# Peripherals.net
KiCad netlist of a schematic drawn in Altium Designer
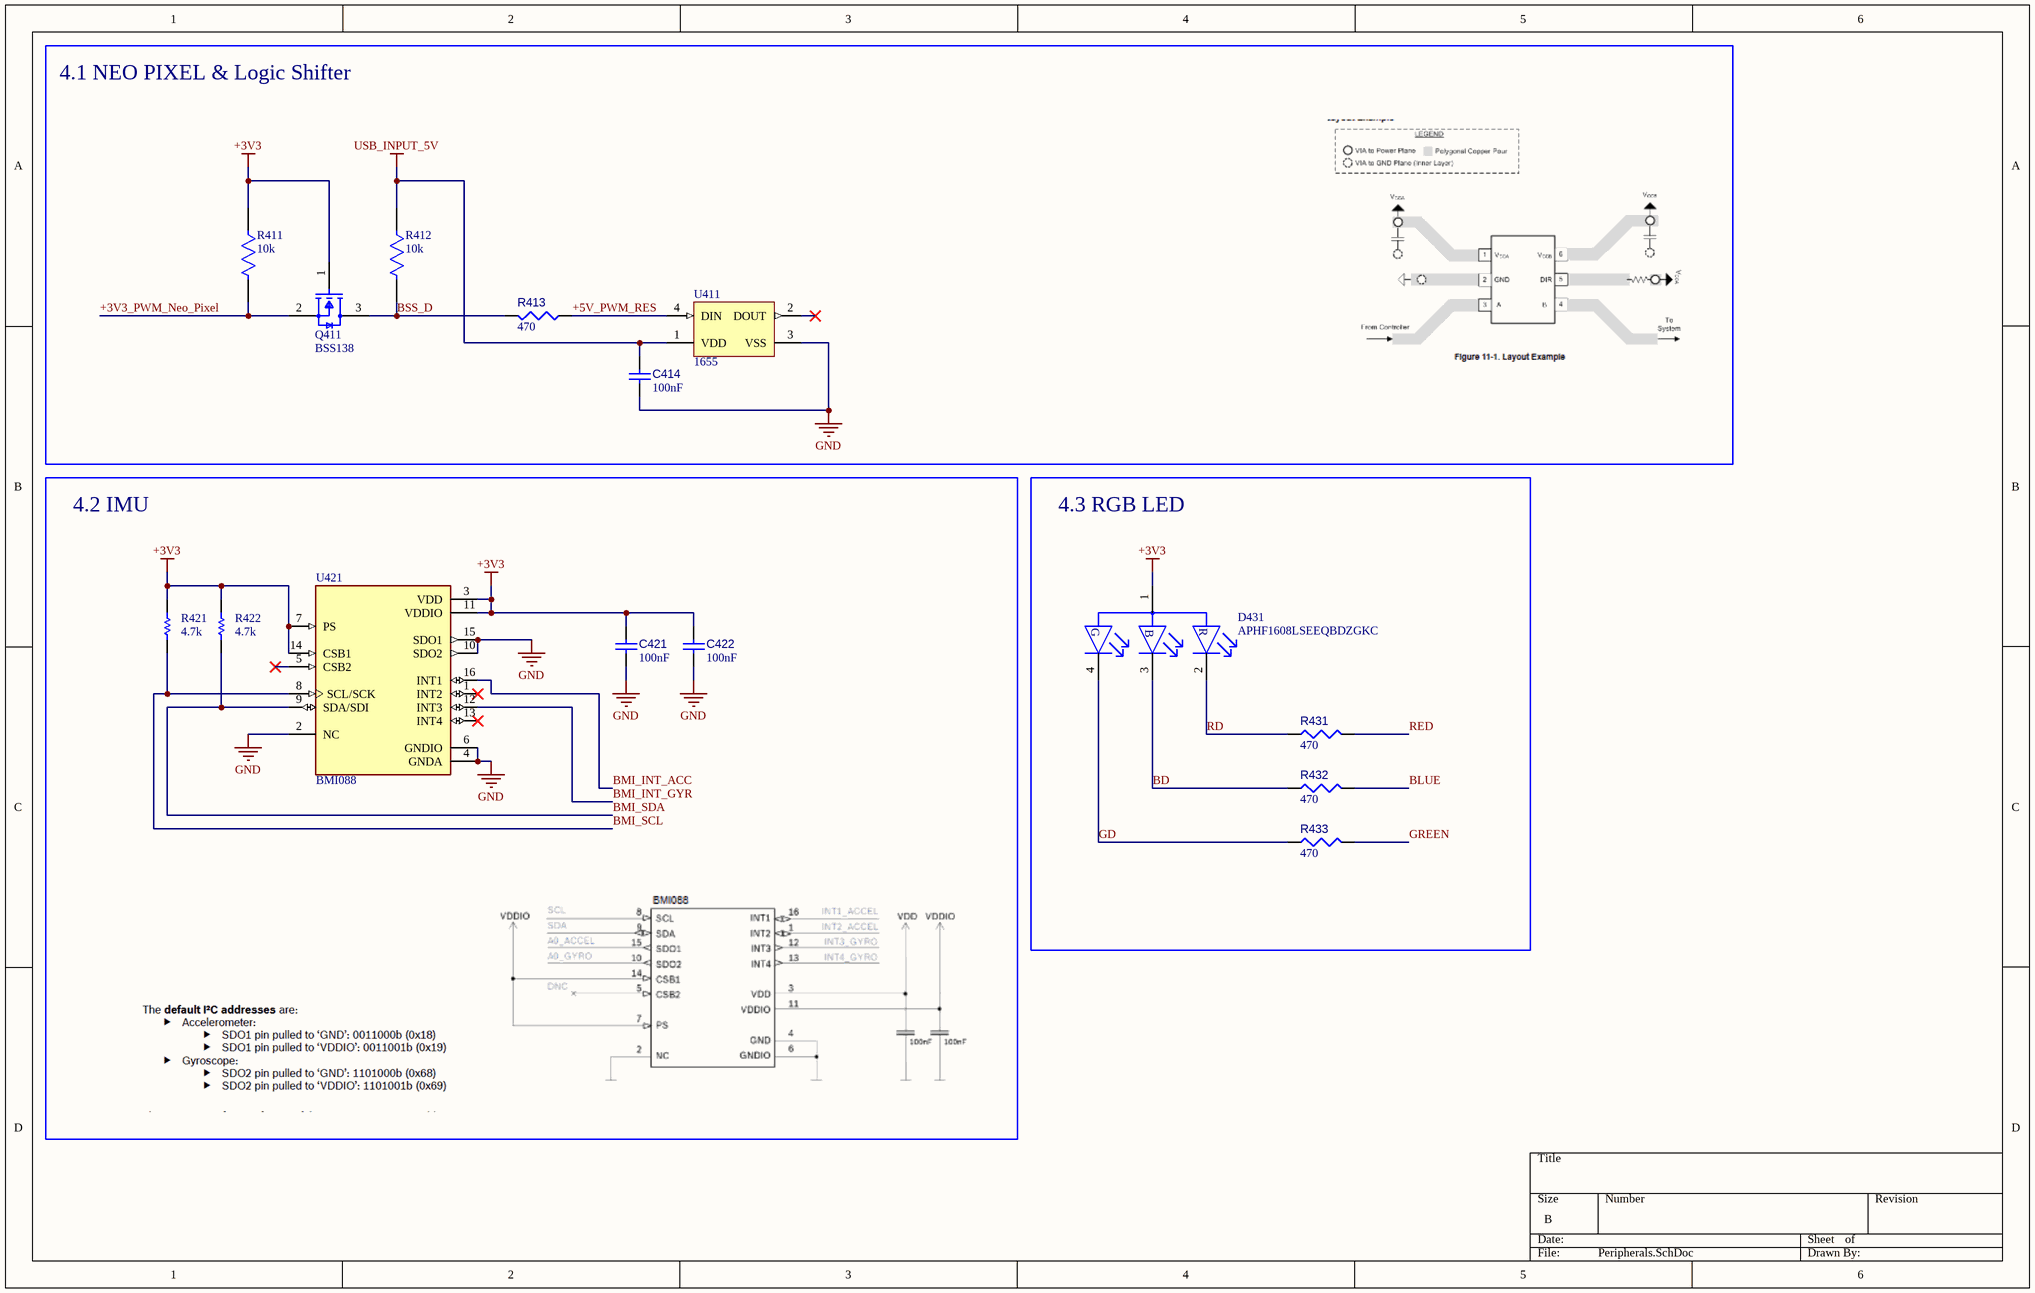
[diagram p0: Peripherals.SchDoc]

(export (version "E")
  (design (tool "Eeschema 10.0.6"))
  (components
    (comp (ref "C414")
      (value "100nF")
      (footprint "CAPC0402(1005)60_L")
      (description "Chip Capacitor, 100nF +/-20%, 10V, 0402, Thickness 0.6 mm")
      (fields (field (name "TOLERANCE") "20%") (field (name "Comment") "Capacitor 100nF +/-20% 10V 0402"))
      (libsource (lib "University of British Columbia") (part "CAP-NP-2"))
    )
    (comp (ref "C421")
      (value "100nF")
      (footprint "CAPC0402(1005)60_L")
      (description "Chip Capacitor, 100nF +/-20%, 10V, 0402, Thickness 0.6 mm")
      (fields (field (name "TOLERANCE") "20%") (field (name "Comment") "Capacitor 100nF +/-20% 10V 0402"))
      (libsource (lib "University of British Columbia") (part "CAP-NP-2"))
    )
    (comp (ref "C422")
      (value "100nF")
      (footprint "CAPC0402(1005)60_L")
      (description "Chip Capacitor, 100nF +/-20%, 10V, 0402, Thickness 0.6 mm")
      (fields (field (name "TOLERANCE") "20%") (field (name "Comment") "Capacitor 100nF +/-20% 10V 0402"))
      (libsource (lib "University of British Columbia") (part "CAP-NP-2"))
    )
    (comp (ref "D431")
      (value "APHF1608LSEEQBDZGKC")
      (footprint "FP-APHF1608LSEEQBDZGKC-MFG")
      (description "LED RGB CLEAR 4SMD")
      (libsource (lib "Altium Content Vault") (part "9e1a3e676f5e2bcfd35a46b8bda8a87"))
    )
    (comp (ref "Q411")
      (value "BSS138")
      (footprint "FP-318-08-IPC_B")
      (libsource (lib "University of British Columbia") (part "3b9c635fedb024a5347a57b145af9cc"))
    )
    (comp (ref "R411")
      (value "10k")
      (footprint "FP-RC0402-0_4-MFG")
      (fields
        (field (name "TOLERANCE") "5%")
        (field (name "POWER") "62.5mW")
        (field (name "Comment") "RC0402JR-0710KL")
      )
      (libsource (lib "University of British Columbia") (part "1029c3af85768c4190bb7ad29bc67b5"))
    )
    (comp (ref "R412")
      (value "10k")
      (footprint "FP-RC0402-0_4-MFG")
      (fields
        (field (name "TOLERANCE") "5%")
        (field (name "POWER") "62.5mW")
        (field (name "Comment") "RC0402JR-0710KL")
      )
      (libsource (lib "University of British Columbia") (part "1029c3af85768c4190bb7ad29bc67b5"))
    )
    (comp (ref "R413")
      (value "470")
      (footprint "RESC0805(2012)_L")
      (description "Chip Resistor, 470 Ohms, +/-5%, 125 mW, -55 to 155 degC, 0805")
      (fields (field (name "TOLERANCE") "5%") (field (name "POWER") "125mW"))
      (libsource (lib "University of British Columbia") (part "RES-2"))
    )
    (comp (ref "R421")
      (value "4.7k")
      (footprint "RESC1609X50X30NL10T20")
      (fields
        (field (name "POWER") "100mW")
        (field (name "TOLERANCE") "1%")
        (field (name "Comment") "CRCW06034K70FKTA")
      )
      (libsource (lib "University of British Columbia") (part "RES"))
    )
    (comp (ref "R422")
      (value "4.7k")
      (footprint "RESC1609X50X30NL10T20")
      (fields
        (field (name "POWER") "100mW")
        (field (name "TOLERANCE") "1%")
        (field (name "Comment") "CRCW06034K70FKTA")
      )
      (libsource (lib "University of British Columbia") (part "RES"))
    )
    (comp (ref "R431")
      (value "470")
      (footprint "RESC0805(2012)_L")
      (description "Chip Resistor, 470 Ohms, +/-5%, 125 mW, -55 to 155 degC, 0805")
      (fields (field (name "TOLERANCE") "5%") (field (name "POWER") "125mW"))
      (libsource (lib "University of British Columbia") (part "RES-2"))
    )
    (comp (ref "R432")
      (value "470")
      (footprint "RESC0805(2012)_L")
      (description "Chip Resistor, 470 Ohms, +/-5%, 125 mW, -55 to 155 degC, 0805")
      (fields (field (name "TOLERANCE") "5%") (field (name "POWER") "125mW"))
      (libsource (lib "University of British Columbia") (part "RES-2"))
    )
    (comp (ref "R433")
      (value "470")
      (footprint "RESC0805(2012)_L")
      (description "Chip Resistor, 470 Ohms, +/-5%, 125 mW, -55 to 155 degC, 0805")
      (fields (field (name "TOLERANCE") "5%") (field (name "POWER") "125mW"))
      (libsource (lib "University of British Columbia") (part "RES-2"))
    )
    (comp (ref "U411")
      (value "1655")
      (footprint "ADA-RGB-1655_V")
      (description "WS2812B 5050 RGB LED WITH INTEGRATED DRIVER CHIP PACK OF 10")
      (libsource (lib "University of British Columbia") (part "ADA-RGB-1655-4"))
    )
    (comp (ref "U421")
      (value "BMI088")
      (footprint "PQFN50P450X300X100-16N")
      (description "BMI088 Series 3.6 V 6 Axis Digital Output Accelerometer Motion Sensor - LGA-16")
      (libsource (lib "University of British Columbia") (part "BMI088"))
    )
  )
  (nets
    (net (code "1") (name "+3V3") (class "Default")
      (node (ref "C421") (pin "2") (pinfunction "2_2") (pintype "passive"))
      (node (ref "C422") (pin "2") (pinfunction "2_2") (pintype "passive"))
      (node (ref "D431") (pin "1") (pinfunction "COMMON_ANODE_1") (pintype "passive"))
      (node (ref "Q411") (pin "1") (pinfunction "G_1") (pintype "passive"))
      (node (ref "R411") (pin "1") (pinfunction "1_1") (pintype "passive"))
      (node (ref "R421") (pin "2") (pinfunction "2_2") (pintype "passive"))
      (node (ref "R422") (pin "2") (pinfunction "2_2") (pintype "passive"))
      (node (ref "U421") (pin "11") (pinfunction "VDDIO_11") (pintype "power_in"))
      (node (ref "U421") (pin "14") (pinfunction "CSB1_14") (pintype "input"))
      (node (ref "U421") (pin "3") (pinfunction "VDD_3") (pintype "power_in"))
      (node (ref "U421") (pin "7") (pinfunction "PS_7") (pintype "input"))
    )
    (net (code "2") (name "/+3V3_PWM_Neo_Pixel") (class "Default")
      (node (ref "Q411") (pin "2") (pinfunction "S_2") (pintype "passive"))
      (node (ref "R411") (pin "2") (pinfunction "2_2") (pintype "passive"))
    )
    (net (code "3") (name "/+5V_PWM_RES") (class "Default")
      (node (ref "R413") (pin "1") (pinfunction "1_1") (pintype "passive"))
      (node (ref "U411") (pin "4") (pinfunction "DIN_4") (pintype "input"))
    )
    (net (code "4") (name "/BD") (class "Default")
      (node (ref "D431") (pin "3") (pinfunction "Blue_C_3") (pintype "passive"))
      (node (ref "R432") (pin "1") (pinfunction "1_1") (pintype "passive"))
    )
    (net (code "5") (name "/BLUE") (class "Default")
      (node (ref "R432") (pin "2") (pinfunction "2_2") (pintype "passive"))
    )
    (net (code "6") (name "/BMI_INT_ACC") (class "Default")
      (node (ref "U421") (pin "16") (pinfunction "INT1_16") (pintype "bidirectional"))
    )
    (net (code "7") (name "/BMI_INT_GYR") (class "Default")
      (node (ref "U421") (pin "12") (pinfunction "INT3_12") (pintype "bidirectional"))
    )
    (net (code "8") (name "/BMI_SCL") (class "Default")
      (node (ref "R421") (pin "1") (pinfunction "1_1") (pintype "passive"))
      (node (ref "U421") (pin "8") (pinfunction "SCL/SCK_8") (pintype "input"))
    )
    (net (code "9") (name "/BMI_SDA") (class "Default")
      (node (ref "R422") (pin "1") (pinfunction "1_1") (pintype "passive"))
      (node (ref "U421") (pin "9") (pinfunction "SDA/SDI_9") (pintype "bidirectional"))
    )
    (net (code "10") (name "/BSS_D") (class "Default")
      (node (ref "Q411") (pin "3") (pinfunction "D_3") (pintype "passive"))
      (node (ref "R412") (pin "2") (pinfunction "2_2") (pintype "passive"))
      (node (ref "R413") (pin "2") (pinfunction "2_2") (pintype "passive"))
    )
    (net (code "11") (name "/GD") (class "Default")
      (node (ref "D431") (pin "4") (pinfunction "Green_C_4") (pintype "passive"))
      (node (ref "R433") (pin "1") (pinfunction "1_1") (pintype "passive"))
    )
    (net (code "12") (name "/GREEN") (class "Default")
      (node (ref "R433") (pin "2") (pinfunction "2_2") (pintype "passive"))
    )
    (net (code "13") (name "/RD") (class "Default")
      (node (ref "D431") (pin "2") (pinfunction "Red_C_2") (pintype "passive"))
      (node (ref "R431") (pin "1") (pinfunction "1_1") (pintype "passive"))
    )
    (net (code "14") (name "/RED") (class "Default")
      (node (ref "R431") (pin "2") (pinfunction "2_2") (pintype "passive"))
    )
    (net (code "15") (name "GND") (class "Default")
      (node (ref "C414") (pin "1") (pinfunction "1_1") (pintype "passive"))
      (node (ref "C421") (pin "1") (pinfunction "1_1") (pintype "passive"))
      (node (ref "C422") (pin "1") (pinfunction "1_1") (pintype "passive"))
      (node (ref "U411") (pin "3") (pinfunction "VSS_3") (pintype "power_in"))
      (node (ref "U421") (pin "10") (pinfunction "SDO2_10") (pintype "output"))
      (node (ref "U421") (pin "15") (pinfunction "SDO1_15") (pintype "output"))
      (node (ref "U421") (pin "2") (pinfunction "NC_2") (pintype "passive"))
      (node (ref "U421") (pin "4") (pinfunction "GNDA_4") (pintype "power_in"))
      (node (ref "U421") (pin "6") (pinfunction "GNDIO_6") (pintype "power_in"))
    )
    (net (code "16") (name "USB_INPUT_5V") (class "Default")
      (node (ref "C414") (pin "2") (pinfunction "2_2") (pintype "passive"))
      (node (ref "R412") (pin "1") (pinfunction "1_1") (pintype "passive"))
      (node (ref "U411") (pin "1") (pinfunction "VDD_1") (pintype "power_in"))
    )
    (net (code "17") (name "unconnected-(U411-DOUT-Pad2)") (class "Default")
      (node (ref "U411") (pin "2") (pinfunction "DOUT_2") (pintype "output+no_connect"))
    )
    (net (code "18") (name "unconnected-(U421-CSB2-Pad5)") (class "Default")
      (node (ref "U421") (pin "5") (pinfunction "CSB2_5") (pintype "input+no_connect"))
    )
    (net (code "19") (name "unconnected-(U421-INT2-Pad1)") (class "Default")
      (node (ref "U421") (pin "1") (pinfunction "INT2_1") (pintype "bidirectional+no_connect"))
    )
    (net (code "20") (name "unconnected-(U421-INT4-Pad13)") (class "Default")
      (node (ref "U421") (pin "13") (pinfunction "INT4_13") (pintype "bidirectional+no_connect"))
    )
  )
)
